# IR2110.net
KiCad netlist of a schematic drawn in Altium Designer
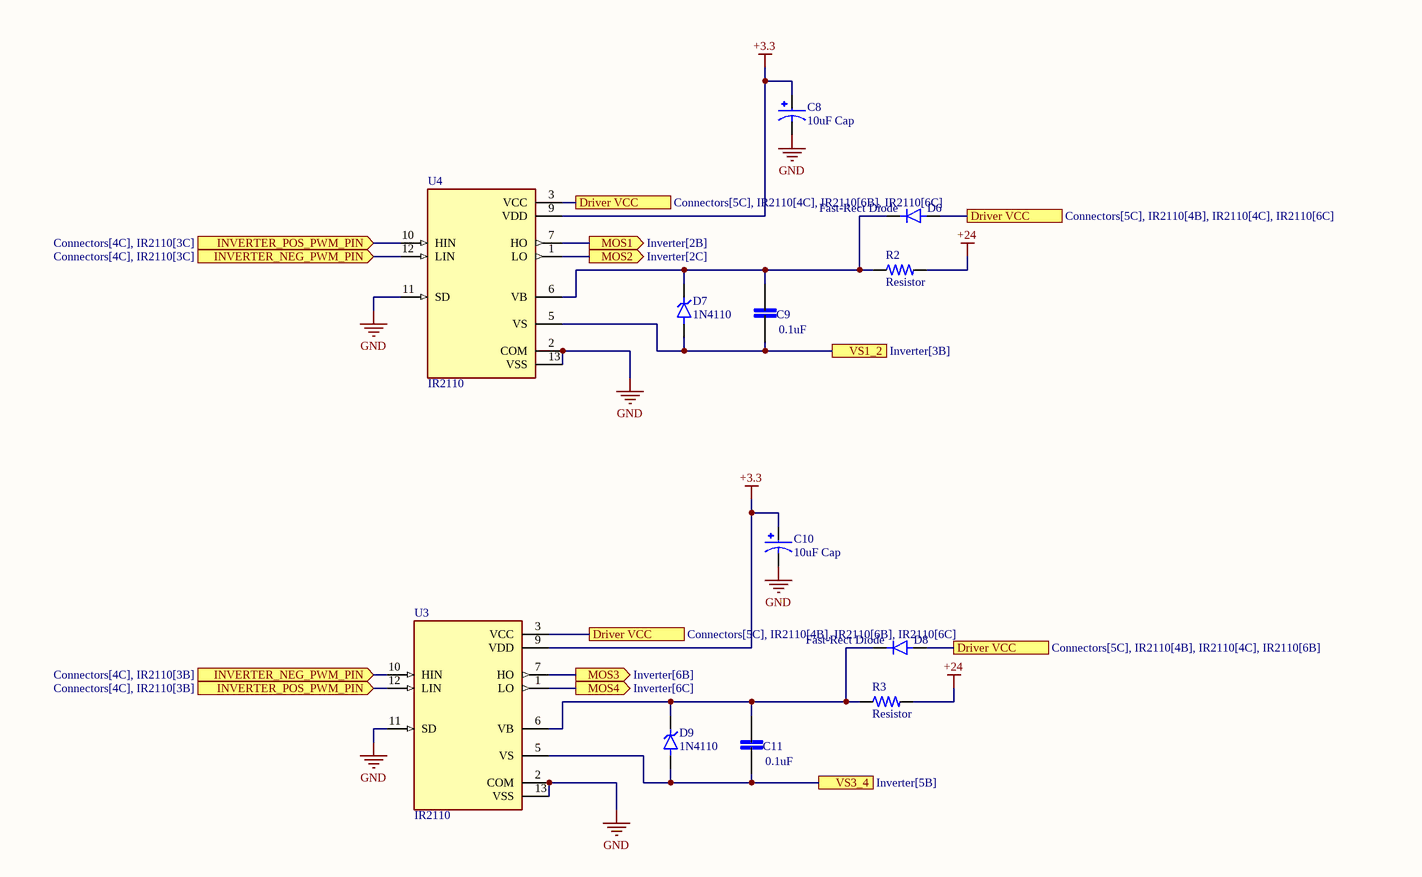
[diagram p0: IR2110.SchDoc]

(export (version "E")
  (design (tool "Eeschema 10.0.6"))
  (components
    (comp (ref "C8")
      (value "10uF Cap")
      (footprint "CAP_10uF")
      (description "CAP ALUM 10UF 20% 50V RADIAL")
      (fields (field (name "MP") "ECE-A1HN100UI") (field (name "MF") "Panasonic"))
      (libsource (lib "MySCH_Library") (part "10uF Cap"))
    )
    (comp (ref "C9")
      (value "0.1uF")
      (footprint "Ceramic Capacitor")
      (fields (field (name "MP") "LD051A121KAB2A") (field (name "MF") "AVX"))
      (libsource (lib "Capacitors Through Hole") (part "Ceramic Capacitor"))
    )
    (comp (ref "C10")
      (value "10uF Cap")
      (footprint "CAP_10uF")
      (description "CAP ALUM 10UF 20% 50V RADIAL")
      (fields (field (name "MP") "ECE-A1HN100UI") (field (name "MF") "Panasonic"))
      (libsource (lib "MySCH_Library") (part "10uF Cap"))
    )
    (comp (ref "C11")
      (value "0.1uF")
      (footprint "Ceramic Capacitor")
      (fields (field (name "MP") "LD051A121KAB2A") (field (name "MF") "AVX"))
      (libsource (lib "Capacitors Through Hole") (part "Ceramic Capacitor"))
    )
    (comp (ref "D6")
      (value "Fast-Rect Diode")
      (footprint "Common Trhough Hole")
      (fields (field (name "MF") "NTE Electronics, Inc.") (field (name "MP") "1N4007"))
      (libsource (lib "Diodes Through Hole") (part "Normal Diode"))
    )
    (comp (ref "D7")
      (value "1N4110")
      (footprint "Common Trhough Hole")
      (fields (field (name "MP") "1SMA5926") (field (name "MF") "Taiwan Semiconductor"))
      (libsource (lib "Diodes Through Hole") (part "Zener Diode"))
    )
    (comp (ref "D8")
      (value "Fast-Rect Diode")
      (footprint "Common Trhough Hole")
      (fields (field (name "MF") "NTE Electronics, Inc.") (field (name "MP") "1N4007"))
      (libsource (lib "Diodes Through Hole") (part "Normal Diode"))
    )
    (comp (ref "D9")
      (value "1N4110")
      (footprint "Common Trhough Hole")
      (fields (field (name "MP") "1SMA5926") (field (name "MF") "Taiwan Semiconductor"))
      (libsource (lib "Diodes Through Hole") (part "Zener Diode"))
    )
    (comp (ref "R2")
      (value "Resistor")
      (footprint "Resistor_Through Hole")
      (fields
        (field (name "MP") "2-2176053-0")
        (field (name "TOLERANCE") "1%")
        (field (name "MF") "TE Connectivity")
      )
      (libsource (lib "Resistors Through Hole") (part "Resistor"))
    )
    (comp (ref "R3")
      (value "Resistor")
      (footprint "Resistor_Through Hole")
      (fields
        (field (name "MP") "2-2176053-0")
        (field (name "TOLERANCE") "1%")
        (field (name "MF") "TE Connectivity")
      )
      (libsource (lib "Resistors Through Hole") (part "Resistor"))
    )
    (comp (ref "U3")
      (value "IR2110")
      (footprint "IR2110")
      (description "Half-Bridge Gate Driver IC Non-Inverting 16-SOIC")
      (fields (field (name "MF") "Infineon"))
      (libsource (lib "MySCH_Library") (part "IR2110"))
    )
    (comp (ref "U4")
      (value "IR2110")
      (footprint "IR2110")
      (description "Half-Bridge Gate Driver IC Non-Inverting 16-SOIC")
      (fields (field (name "MF") "Infineon"))
      (libsource (lib "MySCH_Library") (part "IR2110"))
    )
  )
  (nets
    (net (code "1") (name "+3.3") (class "Default")
      (node (ref "C10") (pin "P") (pinfunction "P_P") (pintype "passive"))
      (node (ref "C8") (pin "P") (pinfunction "P_P") (pintype "passive"))
      (node (ref "U3") (pin "9") (pinfunction "VDD_9") (pintype "power_in"))
      (node (ref "U4") (pin "9") (pinfunction "VDD_9") (pintype "power_in"))
    )
    (net (code "2") (name "+24") (class "Default")
      (node (ref "R2") (pin "2") (pinfunction "2_2") (pintype "passive"))
      (node (ref "R3") (pin "2") (pinfunction "2_2") (pintype "passive"))
    )
    (net (code "3") (name "/Driver VCC") (class "Default")
      (node (ref "D6") (pin "2") (pinfunction "A_2") (pintype "passive"))
      (node (ref "D8") (pin "2") (pinfunction "A_2") (pintype "passive"))
      (node (ref "U3") (pin "3") (pinfunction "VCC_3") (pintype "power_in"))
      (node (ref "U4") (pin "3") (pinfunction "VCC_3") (pintype "power_in"))
    )
    (net (code "4") (name "/INVERTER_NEG_PWM_PIN") (class "Default")
      (node (ref "U3") (pin "10") (pinfunction "HIN_10") (pintype "input"))
      (node (ref "U4") (pin "12") (pinfunction "LIN_12") (pintype "input"))
    )
    (net (code "5") (name "/INVERTER_POS_PWM_PIN") (class "Default")
      (node (ref "U3") (pin "12") (pinfunction "LIN_12") (pintype "input"))
      (node (ref "U4") (pin "10") (pinfunction "HIN_10") (pintype "input"))
    )
    (net (code "6") (name "/MOS1") (class "Default")
      (node (ref "U4") (pin "7") (pinfunction "HO_7") (pintype "output"))
    )
    (net (code "7") (name "/MOS2") (class "Default")
      (node (ref "U4") (pin "1") (pinfunction "LO_1") (pintype "output"))
    )
    (net (code "8") (name "/MOS3") (class "Default")
      (node (ref "U3") (pin "7") (pinfunction "HO_7") (pintype "output"))
    )
    (net (code "9") (name "/MOS4") (class "Default")
      (node (ref "U3") (pin "1") (pinfunction "LO_1") (pintype "output"))
    )
    (net (code "10") (name "/VS1_2") (class "Default")
      (node (ref "C9") (pin "1") (pinfunction "1_1") (pintype "passive"))
      (node (ref "D7") (pin "2") (pinfunction "A_2") (pintype "passive"))
      (node (ref "U4") (pin "5") (pinfunction "VS_5") (pintype "passive"))
    )
    (net (code "11") (name "/VS3_4") (class "Default")
      (node (ref "C11") (pin "1") (pinfunction "1_1") (pintype "passive"))
      (node (ref "D9") (pin "2") (pinfunction "A_2") (pintype "passive"))
      (node (ref "U3") (pin "5") (pinfunction "VS_5") (pintype "passive"))
    )
    (net (code "12") (name "GND") (class "Default")
      (node (ref "C10") (pin "N") (pinfunction "N_N") (pintype "passive"))
      (node (ref "C8") (pin "N") (pinfunction "N_N") (pintype "passive"))
      (node (ref "U3") (pin "11") (pinfunction "SD_11") (pintype "input"))
      (node (ref "U3") (pin "13") (pinfunction "VSS_13") (pintype "power_in"))
      (node (ref "U3") (pin "2") (pinfunction "COM_2") (pintype "power_in"))
      (node (ref "U4") (pin "11") (pinfunction "SD_11") (pintype "input"))
      (node (ref "U4") (pin "13") (pinfunction "VSS_13") (pintype "power_in"))
      (node (ref "U4") (pin "2") (pinfunction "COM_2") (pintype "power_in"))
    )
    (net (code "13") (name "Net-(D6-K)") (class "Default")
      (node (ref "C9") (pin "2") (pinfunction "2_2") (pintype "passive"))
      (node (ref "D6") (pin "1") (pinfunction "K_1") (pintype "passive"))
      (node (ref "D7") (pin "1") (pinfunction "K_1") (pintype "passive"))
      (node (ref "R2") (pin "1") (pinfunction "1_1") (pintype "passive"))
      (node (ref "U4") (pin "6") (pinfunction "VB_6") (pintype "passive"))
    )
    (net (code "14") (name "Net-(D8-K)") (class "Default")
      (node (ref "C11") (pin "2") (pinfunction "2_2") (pintype "passive"))
      (node (ref "D8") (pin "1") (pinfunction "K_1") (pintype "passive"))
      (node (ref "D9") (pin "1") (pinfunction "K_1") (pintype "passive"))
      (node (ref "R3") (pin "1") (pinfunction "1_1") (pintype "passive"))
      (node (ref "U3") (pin "6") (pinfunction "VB_6") (pintype "passive"))
    )
  )
)
